# Sheet1.net
KiCad netlist of a schematic drawn in Altium Designer
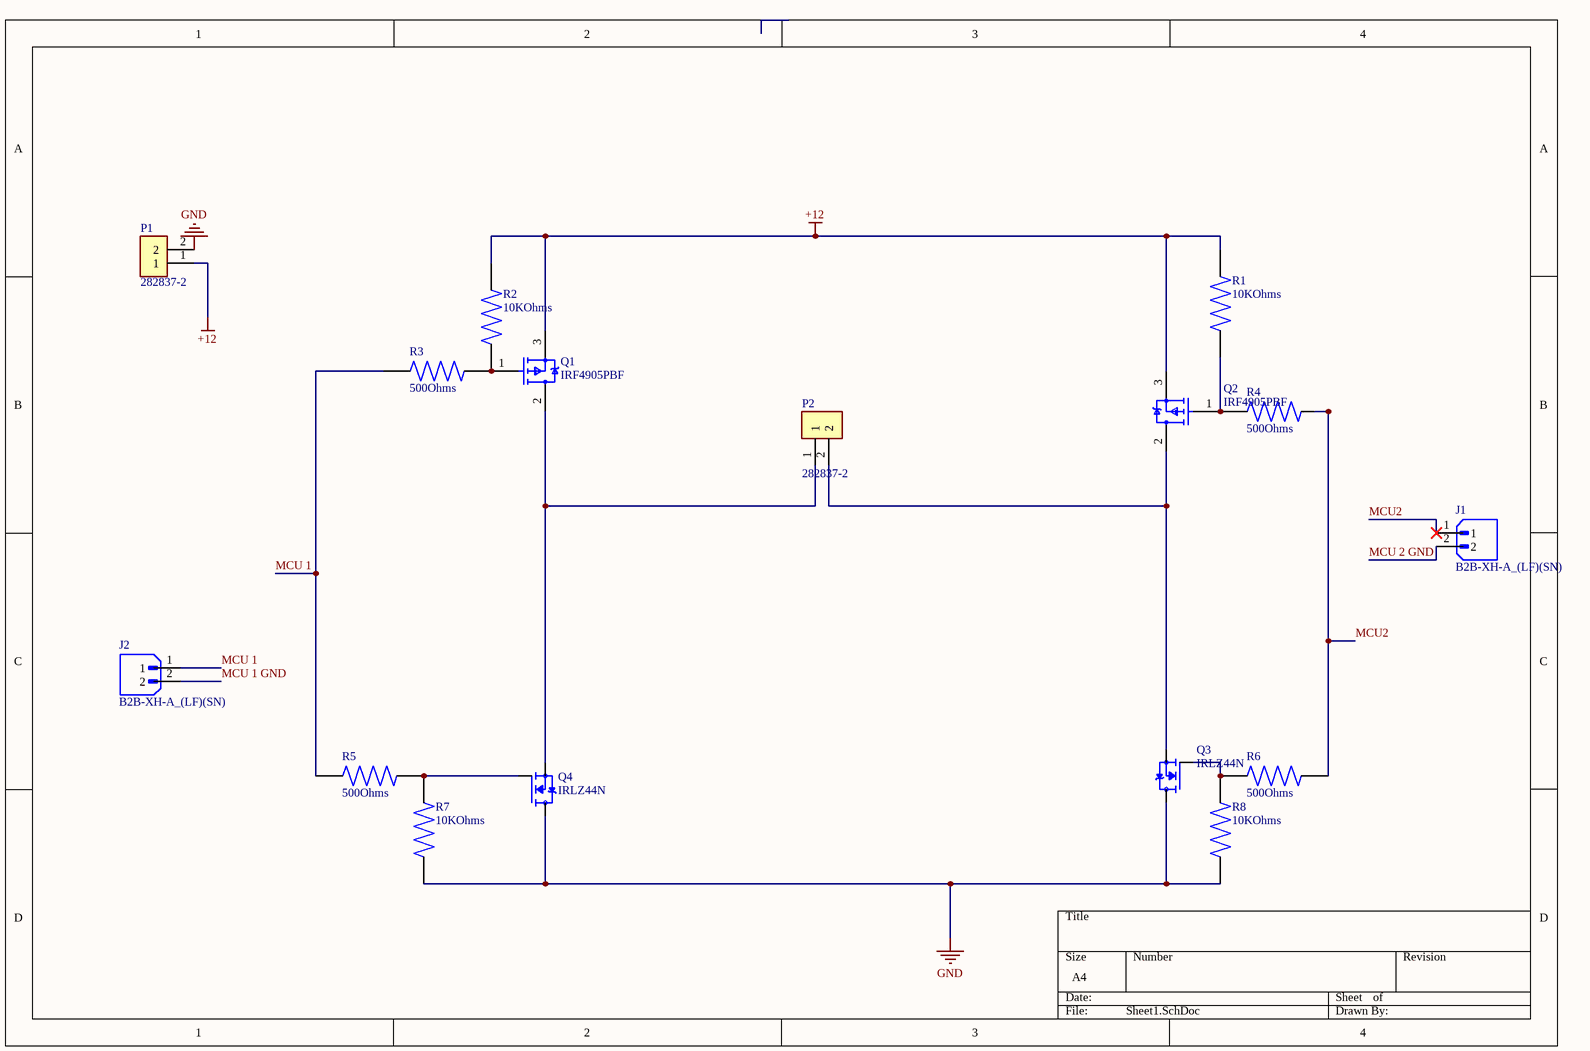
[diagram p0: Sheet1.SchDoc]

(export (version "E")
  (design (tool "Eeschema 10.0.6"))
  (components
    (comp (ref "J1")
      (value "B2B-XH-A_(LF)(SN)")
      (footprint "JST_B2B-XH-A_(LF)(SN)")
      (description "Connector Header Through Hole 2 position 0.098 (2.50mm)")
      (fields (field (name "MF") "JST Sales") (field (name "MP") "B2B-XH-A (LF)(SN)"))
      (libsource (lib "B2B-XH-A__LF__SN_") (part "B2B-XH-A_(LF)(SN)"))
    )
    (comp (ref "J2")
      (value "B2B-XH-A_(LF)(SN)")
      (footprint "JST_B2B-XH-A_(LF)(SN)")
      (description "Connector Header Through Hole 2 position 0.098 (2.50mm)")
      (fields (field (name "MF") "JST Sales") (field (name "MP") "B2B-XH-A (LF)(SN)"))
      (libsource (lib "") (part "B2B-XH-A_(LF)(SN)_1"))
    )
    (comp (ref "P1")
      (value "282837-2")
      (footprint "TE_282837-2")
      (fields (field (name "MF") "TE Connectivity"))
      (libsource (lib "") (part "282837-2_1"))
    )
    (comp (ref "P2")
      (value "282837-2")
      (footprint "TE_282837-2")
      (fields (field (name "MF") "TE Connectivity"))
      (libsource (lib "282837-2") (part "282837-2"))
    )
    (comp (ref "Q1")
      (value "IRF4905PBF")
      (footprint "FP-PG-TO220-3-MFG")
      (description "MOSFET P-CH 55V 74A TO-220AB")
      (libsource (lib "Altium Content Vault") (part "7c43f5ccbd0f8ca8bbf61673af0f16f"))
    )
    (comp (ref "Q2")
      (value "IRF4905PBF")
      (footprint "FP-PG-TO220-3-MFG")
      (description "MOSFET P-CH 55V 74A TO-220AB")
      (libsource (lib "Altium Content Vault") (part "7c43f5ccbd0f8ca8bbf61673af0f16f"))
    )
    (comp (ref "Q3")
      (value "IRLZ44N")
      (footprint "TO254P1054X469X1930-3")
      (description "N-Channel 55 V 47A (Tc) 3.8W (Ta), 110W (Tc) Surface Mount D2PAK")
      (fields (field (name "MF") "Infineon / IR"))
      (libsource (lib "IRLZ44N") (part "IRLZ44N"))
    )
    (comp (ref "Q4")
      (value "IRLZ44N")
      (footprint "TO254P1054X469X1930-3")
      (description "N-Channel 55 V 47A (Tc) 3.8W (Ta), 110W (Tc) Surface Mount D2PAK")
      (fields (field (name "MF") "Infineon / IR"))
      (libsource (lib "IRLZ44N") (part "IRLZ44N"))
    )
    (comp (ref "R1")
      (value "10KOhms")
      (footprint "RESAD1100W55L680D260")
      (description "10.2 kOhms Â±1% 0.25W, 1/4W Through Hole Resistor Axial - Metal Film")
      (fields (field (name "MF") "Yageo") (field (name "MP") "MFR-25FBF52-10K"))
      (libsource (lib "MFR-25FBF52-10K") (part "MFR-25FBF52-10K"))
    )
    (comp (ref "R2")
      (value "10KOhms")
      (footprint "RESAD1100W55L680D260")
      (description "10.2 kOhms Â±1% 0.25W, 1/4W Through Hole Resistor Axial - Metal Film")
      (fields (field (name "MF") "Yageo") (field (name "MP") "MFR-25FBF52-10K"))
      (libsource (lib "MFR-25FBF52-10K") (part "MFR-25FBF52-10K"))
    )
    (comp (ref "R3")
      (value "500Ohms")
      (footprint "RESAD1100W55L680D260")
      (description "10.2 kOhms Â±1% 0.25W, 1/4W Through Hole Resistor Axial - Metal Film")
      (fields (field (name "MF") "Yageo") (field (name "MP") "MFR-25FBF52-10K"))
      (libsource (lib "MFR-25FBF52-10K") (part "MFR-25FBF52-10K"))
    )
    (comp (ref "R4")
      (value "500Ohms")
      (footprint "RESAD1100W55L680D260")
      (description "10.2 kOhms Â±1% 0.25W, 1/4W Through Hole Resistor Axial - Metal Film")
      (fields (field (name "MF") "Yageo") (field (name "MP") "MFR-25FBF52-10K"))
      (libsource (lib "MFR-25FBF52-10K") (part "MFR-25FBF52-10K"))
    )
    (comp (ref "R5")
      (value "500Ohms")
      (footprint "RESAD1100W55L680D260")
      (description "10.2 kOhms Â±1% 0.25W, 1/4W Through Hole Resistor Axial - Metal Film")
      (fields (field (name "MF") "Yageo") (field (name "MP") "MFR-25FBF52-10K"))
      (libsource (lib "MFR-25FBF52-10K") (part "MFR-25FBF52-10K"))
    )
    (comp (ref "R6")
      (value "500Ohms")
      (footprint "RESAD1100W55L680D260")
      (description "10.2 kOhms Â±1% 0.25W, 1/4W Through Hole Resistor Axial - Metal Film")
      (fields (field (name "MF") "Yageo") (field (name "MP") "MFR-25FBF52-10K"))
      (libsource (lib "MFR-25FBF52-10K") (part "MFR-25FBF52-10K"))
    )
    (comp (ref "R7")
      (value "10KOhms")
      (footprint "RESAD1100W55L680D260")
      (description "10.2 kOhms Â±1% 0.25W, 1/4W Through Hole Resistor Axial - Metal Film")
      (fields (field (name "MF") "Yageo") (field (name "MP") "MFR-25FBF52-10K"))
      (libsource (lib "MFR-25FBF52-10K") (part "MFR-25FBF52-10K"))
    )
    (comp (ref "R8")
      (value "10KOhms")
      (footprint "RESAD1100W55L680D260")
      (description "10.2 kOhms Â±1% 0.25W, 1/4W Through Hole Resistor Axial - Metal Film")
      (fields (field (name "MF") "Yageo") (field (name "MP") "MFR-25FBF52-10K"))
      (libsource (lib "MFR-25FBF52-10K") (part "MFR-25FBF52-10K"))
    )
  )
  (nets
    (net (code "1") (name "+12") (class "Default")
      (node (ref "P1") (pin "1") (pinfunction "1_1") (pintype "passive"))
      (node (ref "Q1") (pin "3") (pinfunction "SOURCE_3") (pintype "passive"))
      (node (ref "Q2") (pin "3") (pinfunction "SOURCE_3") (pintype "passive"))
      (node (ref "R1") (pin "1") (pinfunction "1_1") (pintype "passive"))
      (node (ref "R2") (pin "1") (pinfunction "1_1") (pintype "passive"))
    )
    (net (code "2") (name "/MCU 1") (class "Default")
      (node (ref "J2") (pin "1") (pinfunction "1_1") (pintype "passive"))
      (node (ref "R3") (pin "1") (pinfunction "1_1") (pintype "passive"))
      (node (ref "R5") (pin "1") (pinfunction "1_1") (pintype "passive"))
    )
    (net (code "3") (name "/MCU 1 GND") (class "Default")
      (node (ref "J2") (pin "2") (pinfunction "2_2") (pintype "passive"))
    )
    (net (code "4") (name "/MCU 2 GND") (class "Default")
      (node (ref "J1") (pin "2") (pinfunction "2_2") (pintype "passive"))
    )
    (net (code "5") (name "/MCU2") (class "Default")
      (node (ref "J1") (pin "1") (pinfunction "1_1") (pintype "passive"))
      (node (ref "R4") (pin "2") (pinfunction "2_2") (pintype "passive"))
      (node (ref "R6") (pin "2") (pinfunction "2_2") (pintype "passive"))
    )
    (net (code "6") (name "GND") (class "Default")
      (node (ref "P1") (pin "2") (pinfunction "2_2") (pintype "passive"))
      (node (ref "Q3") (pin "2") (pinfunction "D_2") (pintype "passive"))
      (node (ref "Q4") (pin "2") (pinfunction "D_2") (pintype "passive"))
      (node (ref "R7") (pin "2") (pinfunction "2_2") (pintype "passive"))
      (node (ref "R8") (pin "1") (pinfunction "1_1") (pintype "passive"))
    )
    (net (code "7") (name "Net-(Q1-DRAIN)") (class "Default")
      (node (ref "P2") (pin "1") (pinfunction "1_1") (pintype "passive"))
      (node (ref "Q1") (pin "2") (pinfunction "DRAIN_2") (pintype "passive"))
      (node (ref "Q4") (pin "3") (pinfunction "S_3") (pintype "passive"))
    )
    (net (code "8") (name "Net-(Q1-GATE)") (class "Default")
      (node (ref "Q1") (pin "1") (pinfunction "GATE_1") (pintype "passive"))
      (node (ref "R2") (pin "2") (pinfunction "2_2") (pintype "passive"))
      (node (ref "R3") (pin "2") (pinfunction "2_2") (pintype "passive"))
    )
    (net (code "9") (name "Net-(Q2-DRAIN)") (class "Default")
      (node (ref "P2") (pin "2") (pinfunction "2_2") (pintype "passive"))
      (node (ref "Q2") (pin "2") (pinfunction "DRAIN_2") (pintype "passive"))
      (node (ref "Q3") (pin "3") (pinfunction "S_3") (pintype "passive"))
    )
    (net (code "10") (name "Net-(Q2-GATE)") (class "Default")
      (node (ref "Q2") (pin "1") (pinfunction "GATE_1") (pintype "passive"))
      (node (ref "R1") (pin "2") (pinfunction "2_2") (pintype "passive"))
      (node (ref "R4") (pin "1") (pinfunction "1_1") (pintype "passive"))
    )
    (net (code "11") (name "Net-(Q3-G)") (class "Default")
      (node (ref "Q3") (pin "1") (pinfunction "G_1") (pintype "passive"))
      (node (ref "R6") (pin "1") (pinfunction "1_1") (pintype "passive"))
      (node (ref "R8") (pin "2") (pinfunction "2_2") (pintype "passive"))
    )
    (net (code "12") (name "Net-(Q4-G)") (class "Default")
      (node (ref "Q4") (pin "1") (pinfunction "G_1") (pintype "passive"))
      (node (ref "R5") (pin "2") (pinfunction "2_2") (pintype "passive"))
      (node (ref "R7") (pin "1") (pinfunction "1_1") (pintype "passive"))
    )
  )
)
